# mosfet.net
KiCad netlist of a schematic drawn in EAGLE
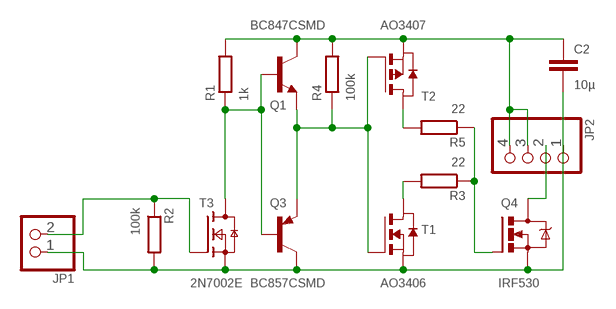
[diagram p0: schematic, sheet 1]

(export (version "E")
  (design (tool "Eeschema 10.0.6"))
  (components
    (comp (ref "C2")
      (value "10µ")
      (footprint "eagle-import:C0805K")
      (libsource (lib "eagle-import") (part "C-EUC0805K"))
    )
    (comp (ref "JP1")
      (value "PINHD-1X2")
      (footprint "eagle-import:1X02")
      (libsource (lib "eagle-import") (part "PINHD-1X2"))
    )
    (comp (ref "JP2")
      (value "PINHD-1X4")
      (footprint "eagle-import:1X04")
      (libsource (lib "eagle-import") (part "PINHD-1X4"))
    )
    (comp (ref "Q1")
      (value "BC847CSMD")
      (footprint "eagle-import:SOT23")
      (libsource (lib "eagle-import") (part "BC847SMDC"))
    )
    (comp (ref "Q3")
      (value "BC857CSMD")
      (footprint "eagle-import:SOT23-BEC")
      (libsource (lib "eagle-import") (part "BC857SMDC"))
    )
    (comp (ref "Q4")
      (value "IRF530")
      (footprint "eagle-import:TO220BV")
      (libsource (lib "eagle-import") (part "IRF530"))
    )
    (comp (ref "R1")
      (value "1k")
      (footprint "eagle-import:R0805")
      (libsource (lib "eagle-import") (part "R-EU_R0805"))
    )
    (comp (ref "R2")
      (value "100k")
      (footprint "eagle-import:R0805")
      (libsource (lib "eagle-import") (part "R-EU_R0805"))
    )
    (comp (ref "R3")
      (value "22")
      (footprint "eagle-import:R0805")
      (libsource (lib "eagle-import") (part "R-EU_R0805"))
    )
    (comp (ref "R4")
      (value "100k")
      (footprint "eagle-import:R0805")
      (libsource (lib "eagle-import") (part "R-EU_R0805"))
    )
    (comp (ref "R5")
      (value "22")
      (footprint "eagle-import:R0805")
      (libsource (lib "eagle-import") (part "R-EU_R0805"))
    )
    (comp (ref "T1")
      (value "AO3406")
      (footprint "eagle-import:SOT-23")
      (libsource (lib "eagle-import") (part "NMOSSOT23"))
    )
    (comp (ref "T2")
      (value "AO3407")
      (footprint "eagle-import:SOT-23")
      (libsource (lib "eagle-import") (part "PMOSSOT23"))
    )
    (comp (ref "T3")
      (value "2N7002E")
      (footprint "eagle-import:SOT23")
      (libsource (lib "eagle-import") (part "2N7002E"))
    )
  )
  (nets
    (net (code "1") (name "Net-(JP2-Pad2)") (class "Default")
      (node (ref "JP2") (pin "2") (pinfunction "2_2") (pintype "passive"))
      (node (ref "Q4") (pin "D") (pinfunction "D_D") (pintype "passive"))
    )
    (net (code "2") (name "Net-(Q1-B)") (class "Default")
      (node (ref "Q1") (pin "1") (pinfunction "B_1") (pintype "passive"))
      (node (ref "Q3") (pin "B") (pinfunction "B_B") (pintype "passive"))
      (node (ref "R1") (pin "1") (pinfunction "1_1") (pintype "passive"))
      (node (ref "T3") (pin "3") (pinfunction "D_3") (pintype "passive"))
    )
    (net (code "3") (name "Net-(Q1-C)") (class "Default")
      (node (ref "C2") (pin "1") (pinfunction "1_1") (pintype "passive"))
      (node (ref "JP2") (pin "3") (pinfunction "3_3") (pintype "passive"))
      (node (ref "JP2") (pin "4") (pinfunction "4_4") (pintype "passive"))
      (node (ref "Q1") (pin "3") (pinfunction "C_3") (pintype "passive"))
      (node (ref "R1") (pin "2") (pinfunction "2_2") (pintype "passive"))
      (node (ref "R4") (pin "2") (pinfunction "2_2") (pintype "passive"))
      (node (ref "T2") (pin "2") (pinfunction "S_2") (pintype "passive"))
    )
    (net (code "4") (name "Net-(Q1-E)") (class "Default")
      (node (ref "Q1") (pin "2") (pinfunction "E_2") (pintype "passive"))
      (node (ref "Q3") (pin "E") (pinfunction "E_E") (pintype "passive"))
      (node (ref "R4") (pin "1") (pinfunction "1_1") (pintype "passive"))
      (node (ref "T1") (pin "3") (pinfunction "G_3") (pintype "passive"))
      (node (ref "T2") (pin "3") (pinfunction "G_3") (pintype "passive"))
    )
    (net (code "5") (name "Net-(Q4-PadG)") (class "Default")
      (node (ref "Q4") (pin "G") (pinfunction "G_G") (pintype "passive"))
      (node (ref "R3") (pin "1") (pinfunction "1_1") (pintype "passive"))
      (node (ref "R5") (pin "1") (pinfunction "1_1") (pintype "passive"))
    )
    (net (code "6") (name "Net-(T1-D)") (class "Default")
      (node (ref "R3") (pin "2") (pinfunction "2_2") (pintype "passive"))
      (node (ref "T1") (pin "1") (pinfunction "D_1") (pintype "passive"))
    )
    (net (code "7") (name "Net-(T1-S)") (class "Default")
      (node (ref "C2") (pin "2") (pinfunction "2_2") (pintype "passive"))
      (node (ref "JP1") (pin "1") (pinfunction "1_1") (pintype "passive"))
      (node (ref "JP2") (pin "1") (pinfunction "1_1") (pintype "passive"))
      (node (ref "Q3") (pin "C") (pinfunction "C_C") (pintype "passive"))
      (node (ref "Q4") (pin "S") (pinfunction "S_S") (pintype "passive"))
      (node (ref "R2") (pin "2") (pinfunction "2_2") (pintype "passive"))
      (node (ref "T1") (pin "2") (pinfunction "S_2") (pintype "passive"))
      (node (ref "T3") (pin "2") (pinfunction "S_2") (pintype "passive"))
    )
    (net (code "8") (name "Net-(T2-D)") (class "Default")
      (node (ref "R5") (pin "2") (pinfunction "2_2") (pintype "passive"))
      (node (ref "T2") (pin "1") (pinfunction "D_1") (pintype "passive"))
    )
    (net (code "9") (name "Net-(T3-G)") (class "Default")
      (node (ref "JP1") (pin "2") (pinfunction "2_2") (pintype "passive"))
      (node (ref "R2") (pin "1") (pinfunction "1_1") (pintype "passive"))
      (node (ref "T3") (pin "1") (pinfunction "G_1") (pintype "passive"))
    )
  )
)
